# Controller2.net
KiCad netlist of a schematic drawn in EAGLE
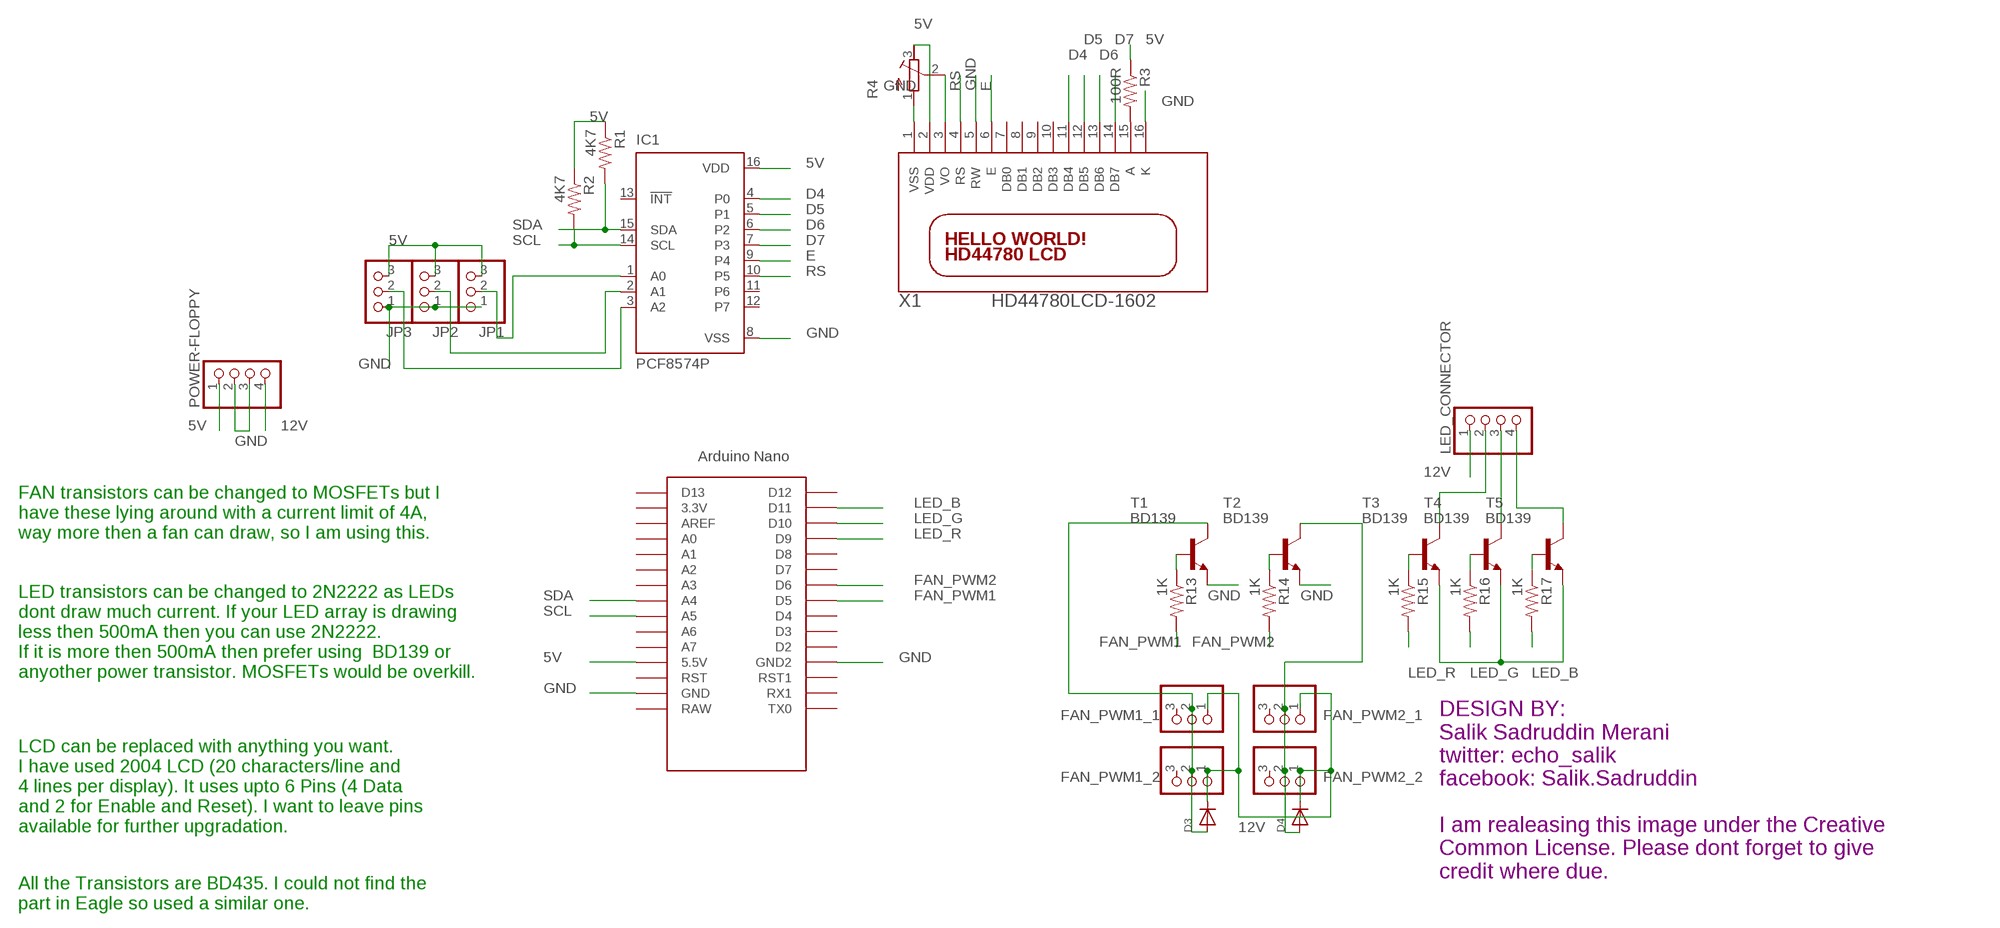
[diagram p0: schematic, sheet 1]

(export (version "E")
  (design (tool "Eeschema 10.0.6"))
  (components
    (comp (ref "D3")
      (value "DIODEDO-1N4148")
      (footprint "eagle-import:DO-1N4148")
      (libsource (lib "eagle-import") (part "DIODEDO-1N4148"))
    )
    (comp (ref "D4")
      (value "DIODEDO-1N4148")
      (footprint "eagle-import:DO-1N4148")
      (libsource (lib "eagle-import") (part "DIODEDO-1N4148"))
    )
    (comp (ref "FAN_PWM1_1")
      (value "PINHD-1X3")
      (footprint "eagle-import:1X03")
      (libsource (lib "eagle-import") (part "PINHD-1X3"))
    )
    (comp (ref "FAN_PWM1_2")
      (value "PINHD-1X3")
      (footprint "eagle-import:1X03")
      (libsource (lib "eagle-import") (part "PINHD-1X3"))
    )
    (comp (ref "FAN_PWM2_1")
      (value "PINHD-1X3")
      (footprint "eagle-import:1X03")
      (libsource (lib "eagle-import") (part "PINHD-1X3"))
    )
    (comp (ref "FAN_PWM2_2")
      (value "PINHD-1X3")
      (footprint "eagle-import:1X03")
      (libsource (lib "eagle-import") (part "PINHD-1X3"))
    )
    (comp (ref "IC1")
      (value "PCF8574P")
      (footprint "eagle-import:DIL16")
      (fields (field (name "MPN") "PCF8574PN"))
      (libsource (lib "eagle-import") (part "PCF8574P"))
    )
    (comp (ref "JP1")
      (value "PINHD-1X3")
      (footprint "eagle-import:1X03")
      (libsource (lib "eagle-import") (part "PINHD-1X3"))
    )
    (comp (ref "JP2")
      (value "PINHD-1X3")
      (footprint "eagle-import:1X03")
      (libsource (lib "eagle-import") (part "PINHD-1X3"))
    )
    (comp (ref "JP3")
      (value "PINHD-1X3")
      (footprint "eagle-import:1X03")
      (libsource (lib "eagle-import") (part "PINHD-1X3"))
    )
    (comp (ref "LED_CONNECTOR")
      (value "PINHD-1X4")
      (footprint "eagle-import:1X04")
      (libsource (lib "eagle-import") (part "PINHD-1X4"))
    )
    (comp (ref "POWER-FLOPPY")
      (value "PINHD-1X4")
      (footprint "eagle-import:1X04")
      (libsource (lib "eagle-import") (part "PINHD-1X4"))
    )
    (comp (ref "R1")
      (value "4K7")
      (footprint "eagle-import:0207_10")
      (libsource (lib "eagle-import") (part "R-US_0207/10"))
    )
    (comp (ref "R2")
      (value "4K7")
      (footprint "eagle-import:0207_10")
      (libsource (lib "eagle-import") (part "R-US_0207/10"))
    )
    (comp (ref "R3")
      (value "100R")
      (footprint "eagle-import:0207_10")
      (libsource (lib "eagle-import") (part "R-US_0207/10"))
    )
    (comp (ref "R4")
      (value "R-TRIMM3339P")
      (footprint "eagle-import:RTRIM3339P")
      (libsource (lib "eagle-import") (part "R-TRIMM3339P"))
    )
    (comp (ref "R13")
      (value "1K")
      (footprint "eagle-import:0207_10")
      (libsource (lib "eagle-import") (part "R-US_0207/10"))
    )
    (comp (ref "R14")
      (value "1K")
      (footprint "eagle-import:0207_10")
      (libsource (lib "eagle-import") (part "R-US_0207/10"))
    )
    (comp (ref "R15")
      (value "1K")
      (footprint "eagle-import:0207_10")
      (libsource (lib "eagle-import") (part "R-US_0207/10"))
    )
    (comp (ref "R16")
      (value "1K")
      (footprint "eagle-import:0207_10")
      (libsource (lib "eagle-import") (part "R-US_0207/10"))
    )
    (comp (ref "R17")
      (value "1K")
      (footprint "eagle-import:0207_10")
      (libsource (lib "eagle-import") (part "R-US_0207/10"))
    )
    (comp (ref "T1")
      (value "BD139")
      (footprint "eagle-import:TO126")
      (libsource (lib "eagle-import") (part "BD139"))
    )
    (comp (ref "T2")
      (value "BD139")
      (footprint "eagle-import:TO126")
      (libsource (lib "eagle-import") (part "BD139"))
    )
    (comp (ref "T3")
      (value "BD139")
      (footprint "eagle-import:TO126")
      (libsource (lib "eagle-import") (part "BD139"))
    )
    (comp (ref "T4")
      (value "BD139")
      (footprint "eagle-import:TO126")
      (libsource (lib "eagle-import") (part "BD139"))
    )
    (comp (ref "T5")
      (value "BD139")
      (footprint "eagle-import:TO126")
      (libsource (lib "eagle-import") (part "BD139"))
    )
    (comp (ref "U$1")
      (value "NANO")
      (footprint "eagle-import:NANO")
      (libsource (lib "eagle-import") (part "NANO"))
    )
    (comp (ref "X1")
      (value "HD44780LCD-1602")
      (footprint "eagle-import:LCD1602")
      (libsource (lib "eagle-import") (part "HD44780LCD-1602"))
    )
  )
  (nets
    (net (code "1") (name "/5V") (class "Default")
      (node (ref "IC1") (pin "16") (pinfunction "VDD_16") (pintype "power_in"))
      (node (ref "JP1") (pin "3") (pinfunction "3_3") (pintype "passive"))
      (node (ref "JP2") (pin "3") (pinfunction "3_3") (pintype "passive"))
      (node (ref "JP3") (pin "3") (pinfunction "3_3") (pintype "passive"))
      (node (ref "POWER-FLOPPY") (pin "1") (pinfunction "1_1") (pintype "passive"))
      (node (ref "R1") (pin "1") (pinfunction "1_1") (pintype "passive"))
      (node (ref "R2") (pin "1") (pinfunction "1_1") (pintype "passive"))
      (node (ref "R3") (pin "1") (pinfunction "1_1") (pintype "passive"))
      (node (ref "R4") (pin "3") (pinfunction "E_3") (pintype "passive"))
      (node (ref "U$1") (pin "5V") (pinfunction "5.5V_5V") (pintype "bidirectional"))
      (node (ref "X1") (pin "2") (pinfunction "VDD_2") (pintype "power_in"))
    )
    (net (code "2") (name "/12V") (class "Default")
      (node (ref "D3") (pin "C") (pinfunction "C_C") (pintype "passive"))
      (node (ref "D4") (pin "C") (pinfunction "C_C") (pintype "passive"))
      (node (ref "FAN_PWM1_1") (pin "1") (pinfunction "1_1") (pintype "passive"))
      (node (ref "FAN_PWM1_2") (pin "1") (pinfunction "1_1") (pintype "passive"))
      (node (ref "FAN_PWM2_1") (pin "1") (pinfunction "1_1") (pintype "passive"))
      (node (ref "FAN_PWM2_2") (pin "1") (pinfunction "1_1") (pintype "passive"))
      (node (ref "LED_CONNECTOR") (pin "1") (pinfunction "1_1") (pintype "passive"))
      (node (ref "POWER-FLOPPY") (pin "4") (pinfunction "4_4") (pintype "passive"))
    )
    (net (code "3") (name "/D4") (class "Default")
      (node (ref "IC1") (pin "4") (pinfunction "P0_4") (pintype "bidirectional"))
      (node (ref "X1") (pin "11") (pinfunction "DB4_11") (pintype "bidirectional"))
    )
    (net (code "4") (name "/D5") (class "Default")
      (node (ref "IC1") (pin "5") (pinfunction "P1_5") (pintype "bidirectional"))
      (node (ref "X1") (pin "12") (pinfunction "DB5_12") (pintype "bidirectional"))
    )
    (net (code "5") (name "/D6") (class "Default")
      (node (ref "IC1") (pin "6") (pinfunction "P2_6") (pintype "bidirectional"))
      (node (ref "X1") (pin "13") (pinfunction "DB6_13") (pintype "bidirectional"))
    )
    (net (code "6") (name "/D7") (class "Default")
      (node (ref "IC1") (pin "7") (pinfunction "P3_7") (pintype "bidirectional"))
      (node (ref "X1") (pin "14") (pinfunction "DB7_14") (pintype "bidirectional"))
    )
    (net (code "7") (name "/E") (class "Default")
      (node (ref "IC1") (pin "9") (pinfunction "P4_9") (pintype "bidirectional"))
      (node (ref "X1") (pin "6") (pinfunction "E_6") (pintype "input"))
    )
    (net (code "8") (name "/FAN_PWM1") (class "Default")
      (node (ref "R13") (pin "2") (pinfunction "2_2") (pintype "passive"))
      (node (ref "U$1") (pin "D5") (pinfunction "D5_D5") (pintype "bidirectional"))
    )
    (net (code "9") (name "/FAN_PWM2") (class "Default")
      (node (ref "R14") (pin "2") (pinfunction "2_2") (pintype "passive"))
      (node (ref "U$1") (pin "D6") (pinfunction "D6_D6") (pintype "bidirectional"))
    )
    (net (code "10") (name "/GND") (class "Default")
      (node (ref "IC1") (pin "8") (pinfunction "VSS_8") (pintype "power_in"))
      (node (ref "JP1") (pin "1") (pinfunction "1_1") (pintype "passive"))
      (node (ref "JP2") (pin "1") (pinfunction "1_1") (pintype "passive"))
      (node (ref "JP3") (pin "1") (pinfunction "1_1") (pintype "passive"))
      (node (ref "POWER-FLOPPY") (pin "2") (pinfunction "2_2") (pintype "passive"))
      (node (ref "POWER-FLOPPY") (pin "3") (pinfunction "3_3") (pintype "passive"))
      (node (ref "R4") (pin "1") (pinfunction "A_1") (pintype "passive"))
      (node (ref "T1") (pin "1") (pinfunction "E_1") (pintype "passive"))
      (node (ref "T2") (pin "1") (pinfunction "E_1") (pintype "passive"))
      (node (ref "U$1") (pin "GND") (pinfunction "GND_GND") (pintype "bidirectional"))
      (node (ref "U$1") (pin "GND1") (pinfunction "GND2_GND1") (pintype "bidirectional"))
      (node (ref "X1") (pin "1") (pinfunction "VSS_1") (pintype "power_in"))
      (node (ref "X1") (pin "16") (pinfunction "K_16") (pintype "input"))
      (node (ref "X1") (pin "5") (pinfunction "RW_5") (pintype "input"))
    )
    (net (code "11") (name "/LED_B") (class "Default")
      (node (ref "R17") (pin "2") (pinfunction "2_2") (pintype "passive"))
      (node (ref "U$1") (pin "D11") (pinfunction "D11_D11") (pintype "bidirectional"))
    )
    (net (code "12") (name "/LED_G") (class "Default")
      (node (ref "R16") (pin "2") (pinfunction "2_2") (pintype "passive"))
      (node (ref "U$1") (pin "D10") (pinfunction "D10_D10") (pintype "bidirectional"))
    )
    (net (code "13") (name "/LED_R") (class "Default")
      (node (ref "R15") (pin "2") (pinfunction "2_2") (pintype "passive"))
      (node (ref "U$1") (pin "D9") (pinfunction "D9_D9") (pintype "bidirectional"))
    )
    (net (code "14") (name "/RS") (class "Default")
      (node (ref "IC1") (pin "10") (pinfunction "P5_10") (pintype "bidirectional"))
      (node (ref "X1") (pin "4") (pinfunction "RS_4") (pintype "input"))
    )
    (net (code "15") (name "/SCL") (class "Default")
      (node (ref "IC1") (pin "14") (pinfunction "SCL_14") (pintype "input"))
      (node (ref "R2") (pin "2") (pinfunction "2_2") (pintype "passive"))
      (node (ref "U$1") (pin "A5") (pinfunction "A5_A5") (pintype "bidirectional"))
    )
    (net (code "16") (name "/SDA") (class "Default")
      (node (ref "IC1") (pin "15") (pinfunction "SDA_15") (pintype "bidirectional"))
      (node (ref "R1") (pin "2") (pinfunction "2_2") (pintype "passive"))
      (node (ref "U$1") (pin "A4") (pinfunction "A4_A4") (pintype "bidirectional"))
    )
    (net (code "17") (name "Net-(IC1-A0)") (class "Default")
      (node (ref "IC1") (pin "1") (pinfunction "A0_1") (pintype "input"))
      (node (ref "JP1") (pin "2") (pinfunction "2_2") (pintype "passive"))
    )
    (net (code "18") (name "Net-(IC1-A1)") (class "Default")
      (node (ref "IC1") (pin "2") (pinfunction "A1_2") (pintype "input"))
      (node (ref "JP2") (pin "2") (pinfunction "2_2") (pintype "passive"))
    )
    (net (code "19") (name "Net-(IC1-A2)") (class "Default")
      (node (ref "IC1") (pin "3") (pinfunction "A2_3") (pintype "input"))
      (node (ref "JP3") (pin "2") (pinfunction "2_2") (pintype "passive"))
    )
    (net (code "20") (name "Net-(R4-S)") (class "Default")
      (node (ref "R4") (pin "2") (pinfunction "S_2") (pintype "passive"))
      (node (ref "X1") (pin "3") (pinfunction "VO_3") (pintype "input"))
    )
    (net (code "21") (name "Net-(T1-B)") (class "Default")
      (node (ref "R13") (pin "1") (pinfunction "1_1") (pintype "passive"))
      (node (ref "T1") (pin "3") (pinfunction "B_3") (pintype "passive"))
    )
    (net (code "22") (name "Net-(T1-C)") (class "Default")
      (node (ref "D3") (pin "A") (pinfunction "A_A") (pintype "passive"))
      (node (ref "FAN_PWM1_1") (pin "2") (pinfunction "2_2") (pintype "passive"))
      (node (ref "FAN_PWM1_2") (pin "2") (pinfunction "2_2") (pintype "passive"))
      (node (ref "T1") (pin "2") (pinfunction "C_2") (pintype "passive"))
    )
    (net (code "23") (name "Net-(T2-B)") (class "Default")
      (node (ref "R14") (pin "1") (pinfunction "1_1") (pintype "passive"))
      (node (ref "T2") (pin "3") (pinfunction "B_3") (pintype "passive"))
    )
    (net (code "24") (name "Net-(T2-C)") (class "Default")
      (node (ref "D4") (pin "A") (pinfunction "A_A") (pintype "passive"))
      (node (ref "FAN_PWM2_1") (pin "2") (pinfunction "2_2") (pintype "passive"))
      (node (ref "FAN_PWM2_2") (pin "2") (pinfunction "2_2") (pintype "passive"))
      (node (ref "T2") (pin "2") (pinfunction "C_2") (pintype "passive"))
    )
    (net (code "25") (name "Net-(T3-B)") (class "Default")
      (node (ref "R15") (pin "1") (pinfunction "1_1") (pintype "passive"))
      (node (ref "T3") (pin "3") (pinfunction "B_3") (pintype "passive"))
    )
    (net (code "26") (name "Net-(T3-C)") (class "Default")
      (node (ref "LED_CONNECTOR") (pin "2") (pinfunction "2_2") (pintype "passive"))
      (node (ref "T3") (pin "2") (pinfunction "C_2") (pintype "passive"))
    )
    (net (code "27") (name "Net-(T3-E)") (class "Default")
      (node (ref "T3") (pin "1") (pinfunction "E_1") (pintype "passive"))
      (node (ref "T4") (pin "1") (pinfunction "E_1") (pintype "passive"))
      (node (ref "T5") (pin "1") (pinfunction "E_1") (pintype "passive"))
    )
    (net (code "28") (name "Net-(T4-B)") (class "Default")
      (node (ref "R16") (pin "1") (pinfunction "1_1") (pintype "passive"))
      (node (ref "T4") (pin "3") (pinfunction "B_3") (pintype "passive"))
    )
    (net (code "29") (name "Net-(T4-C)") (class "Default")
      (node (ref "LED_CONNECTOR") (pin "3") (pinfunction "3_3") (pintype "passive"))
      (node (ref "T4") (pin "2") (pinfunction "C_2") (pintype "passive"))
    )
    (net (code "30") (name "Net-(T5-B)") (class "Default")
      (node (ref "R17") (pin "1") (pinfunction "1_1") (pintype "passive"))
      (node (ref "T5") (pin "3") (pinfunction "B_3") (pintype "passive"))
    )
    (net (code "31") (name "Net-(T5-C)") (class "Default")
      (node (ref "LED_CONNECTOR") (pin "4") (pinfunction "4_4") (pintype "passive"))
      (node (ref "T5") (pin "2") (pinfunction "C_2") (pintype "passive"))
    )
    (net (code "32") (name "Net-(X1-A)") (class "Default")
      (node (ref "R3") (pin "2") (pinfunction "2_2") (pintype "passive"))
      (node (ref "X1") (pin "15") (pinfunction "A_15") (pintype "input"))
    )
    (net (code "33") (name "unconnected-(FAN_PWM1_1-Pad3)") (class "Default")
      (node (ref "FAN_PWM1_1") (pin "3") (pinfunction "3_3") (pintype "passive"))
    )
    (net (code "34") (name "unconnected-(FAN_PWM1_2-Pad3)") (class "Default")
      (node (ref "FAN_PWM1_2") (pin "3") (pinfunction "3_3") (pintype "passive"))
    )
    (net (code "35") (name "unconnected-(FAN_PWM2_1-Pad3)") (class "Default")
      (node (ref "FAN_PWM2_1") (pin "3") (pinfunction "3_3") (pintype "passive"))
    )
    (net (code "36") (name "unconnected-(FAN_PWM2_2-Pad3)") (class "Default")
      (node (ref "FAN_PWM2_2") (pin "3") (pinfunction "3_3") (pintype "passive"))
    )
    (net (code "37") (name "unconnected-(IC1-P6-Pad11)") (class "Default")
      (node (ref "IC1") (pin "11") (pinfunction "P6_11") (pintype "bidirectional"))
    )
    (net (code "38") (name "unconnected-(IC1-P7-Pad12)") (class "Default")
      (node (ref "IC1") (pin "12") (pinfunction "P7_12") (pintype "bidirectional"))
    )
    (net (code "39") (name "unconnected-(IC1-~{INT}-Pad13)") (class "Default")
      (node (ref "IC1") (pin "13") (pinfunction "~{INT}_13") (pintype "output"))
    )
    (net (code "40") (name "unconnected-(U$1-Pad3.3V)") (class "Default")
      (node (ref "U$1") (pin "3.3V") (pinfunction "3.3V_3.3V") (pintype "bidirectional"))
    )
    (net (code "41") (name "unconnected-(U$1-PadA0)") (class "Default")
      (node (ref "U$1") (pin "A0") (pinfunction "A0_A0") (pintype "bidirectional"))
    )
    (net (code "42") (name "unconnected-(U$1-PadA1)") (class "Default")
      (node (ref "U$1") (pin "A1") (pinfunction "A1_A1") (pintype "bidirectional"))
    )
    (net (code "43") (name "unconnected-(U$1-PadA2)") (class "Default")
      (node (ref "U$1") (pin "A2") (pinfunction "A2_A2") (pintype "bidirectional"))
    )
    (net (code "44") (name "unconnected-(U$1-PadA3)") (class "Default")
      (node (ref "U$1") (pin "A3") (pinfunction "A3_A3") (pintype "bidirectional"))
    )
    (net (code "45") (name "unconnected-(U$1-PadA6)") (class "Default")
      (node (ref "U$1") (pin "A6") (pinfunction "A6_A6") (pintype "bidirectional"))
    )
    (net (code "46") (name "unconnected-(U$1-PadA7)") (class "Default")
      (node (ref "U$1") (pin "A7") (pinfunction "A7_A7") (pintype "bidirectional"))
    )
    (net (code "47") (name "unconnected-(U$1-PadAREF)") (class "Default")
      (node (ref "U$1") (pin "AREF") (pinfunction "AREF_AREF") (pintype "bidirectional"))
    )
    (net (code "48") (name "unconnected-(U$1-PadD2)") (class "Default")
      (node (ref "U$1") (pin "D2") (pinfunction "D2_D2") (pintype "bidirectional"))
    )
    (net (code "49") (name "unconnected-(U$1-PadD3)") (class "Default")
      (node (ref "U$1") (pin "D3") (pinfunction "D3_D3") (pintype "bidirectional"))
    )
    (net (code "50") (name "unconnected-(U$1-PadD4)") (class "Default")
      (node (ref "U$1") (pin "D4") (pinfunction "D4_D4") (pintype "bidirectional"))
    )
    (net (code "51") (name "unconnected-(U$1-PadD7)") (class "Default")
      (node (ref "U$1") (pin "D7") (pinfunction "D7_D7") (pintype "bidirectional"))
    )
    (net (code "52") (name "unconnected-(U$1-PadD8)") (class "Default")
      (node (ref "U$1") (pin "D8") (pinfunction "D8_D8") (pintype "bidirectional"))
    )
    (net (code "53") (name "unconnected-(U$1-PadD12)") (class "Default")
      (node (ref "U$1") (pin "D12") (pinfunction "D12_D12") (pintype "bidirectional"))
    )
    (net (code "54") (name "unconnected-(U$1-PadD13)") (class "Default")
      (node (ref "U$1") (pin "D13") (pinfunction "D13_D13") (pintype "bidirectional"))
    )
    (net (code "55") (name "unconnected-(U$1-PadICSP1)") (class "Default")
      (node (ref "U$1") (pin "ICSP1") (pinfunction "ICSP1_ICSP1") (pintype "bidirectional"))
    )
    (net (code "56") (name "unconnected-(U$1-PadICSP2)") (class "Default")
      (node (ref "U$1") (pin "ICSP2") (pinfunction "ICSP2_ICSP2") (pintype "bidirectional"))
    )
    (net (code "57") (name "unconnected-(U$1-PadICSP3)") (class "Default")
      (node (ref "U$1") (pin "ICSP3") (pinfunction "ICSP3_ICSP3") (pintype "bidirectional"))
    )
    (net (code "58") (name "unconnected-(U$1-PadICSP4)") (class "Default")
      (node (ref "U$1") (pin "ICSP4") (pinfunction "ICSP4_ICSP4") (pintype "bidirectional"))
    )
    (net (code "59") (name "unconnected-(U$1-PadICSP5)") (class "Default")
      (node (ref "U$1") (pin "ICSP5") (pinfunction "ICSP5_ICSP5") (pintype "bidirectional"))
    )
    (net (code "60") (name "unconnected-(U$1-PadICSP6)") (class "Default")
      (node (ref "U$1") (pin "ICSP6") (pinfunction "ICSP6_ICSP6") (pintype "bidirectional"))
    )
    (net (code "61") (name "unconnected-(U$1-PadRAW)") (class "Default")
      (node (ref "U$1") (pin "RAW") (pinfunction "RAW_RAW") (pintype "bidirectional"))
    )
    (net (code "62") (name "unconnected-(U$1-PadRST)") (class "Default")
      (node (ref "U$1") (pin "RST") (pinfunction "RST_RST") (pintype "bidirectional"))
    )
    (net (code "63") (name "unconnected-(U$1-PadRST1)") (class "Default")
      (node (ref "U$1") (pin "RST1") (pinfunction "RST1_RST1") (pintype "bidirectional"))
    )
    (net (code "64") (name "unconnected-(U$1-PadRX1)") (class "Default")
      (node (ref "U$1") (pin "RX1") (pinfunction "RX1_RX1") (pintype "bidirectional"))
    )
    (net (code "65") (name "unconnected-(U$1-PadTX0)") (class "Default")
      (node (ref "U$1") (pin "TX0") (pinfunction "TX0_TX0") (pintype "bidirectional"))
    )
    (net (code "66") (name "unconnected-(X1-DB0-Pad7)") (class "Default")
      (node (ref "X1") (pin "7") (pinfunction "DB0_7") (pintype "bidirectional"))
    )
    (net (code "67") (name "unconnected-(X1-DB1-Pad8)") (class "Default")
      (node (ref "X1") (pin "8") (pinfunction "DB1_8") (pintype "bidirectional"))
    )
    (net (code "68") (name "unconnected-(X1-DB2-Pad9)") (class "Default")
      (node (ref "X1") (pin "9") (pinfunction "DB2_9") (pintype "bidirectional"))
    )
    (net (code "69") (name "unconnected-(X1-DB3-Pad10)") (class "Default")
      (node (ref "X1") (pin "10") (pinfunction "DB3_10") (pintype "bidirectional"))
    )
  )
)
